# PowerReg.net
KiCad netlist of a schematic drawn in EAGLE
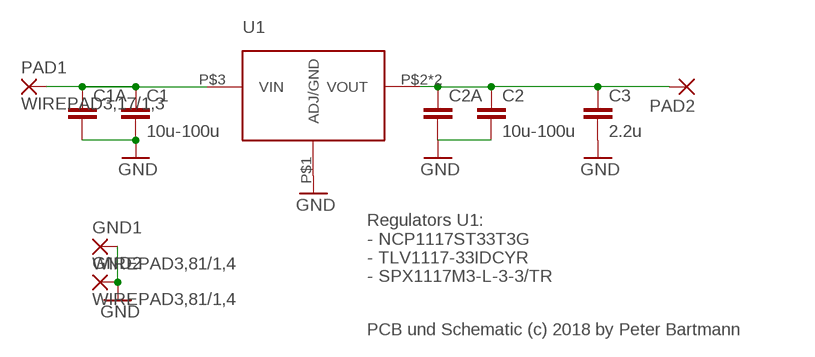
[diagram p0: schematic, sheet 1]

(export (version "E")
  (design (tool "Eeschema 10.0.6"))
  (components
    (comp (ref "C1")
      (value "10u-100u")
      (footprint "eagle-import:C0805")
      (libsource (lib "eagle-import") (part "rcl_334_C-EUC0805"))
    )
    (comp (ref "C1A")
      (value "C-EUC1210K")
      (footprint "eagle-import:C1210K")
      (libsource (lib "eagle-import") (part "C-EUC1210K"))
    )
    (comp (ref "C2")
      (value "10u-100u")
      (footprint "eagle-import:C0805")
      (libsource (lib "eagle-import") (part "rcl_334_C-EUC0805"))
    )
    (comp (ref "C2A")
      (value "C-EUC1210K")
      (footprint "eagle-import:C1210K")
      (libsource (lib "eagle-import") (part "C-EUC1210K"))
    )
    (comp (ref "C3")
      (value "2.2u")
      (footprint "eagle-import:C0603")
      (libsource (lib "eagle-import") (part "C-EUC0603"))
    )
    (comp (ref "GND1")
      (value "WIREPAD3,81/1,4")
      (footprint "eagle-import:3,81_1,4")
      (libsource (lib "eagle-import") (part "WIREPAD3,81/1,4"))
    )
    (comp (ref "GND2")
      (value "WIREPAD3,81/1,4")
      (footprint "eagle-import:3,81_1,4")
      (libsource (lib "eagle-import") (part "WIREPAD3,81/1,4"))
    )
    (comp (ref "PAD1")
      (value "WIREPAD3,17/1,3")
      (footprint "eagle-import:3,17_1,3")
      (libsource (lib "eagle-import") (part "WIREPAD3,17/1,3"))
    )
    (comp (ref "PAD2")
      (value "SMD5")
      (footprint "eagle-import:SMD2,54-5,08")
      (libsource (lib "eagle-import") (part "SMD5"))
    )
    (comp (ref "U1")
      (value "SPX1117")
      (footprint "eagle-import:SOT-223")
      (libsource (lib "eagle-import") (part "SPX1117"))
    )
  )
  (nets
    (net (code "1") (name "GND") (class "Default")
      (node (ref "C1") (pin "2") (pinfunction "2_2") (pintype "passive"))
      (node (ref "C1A") (pin "2") (pinfunction "2_2") (pintype "passive"))
      (node (ref "C2") (pin "2") (pinfunction "2_2") (pintype "passive"))
      (node (ref "C2A") (pin "2") (pinfunction "2_2") (pintype "passive"))
      (node (ref "C3") (pin "2") (pinfunction "2_2") (pintype "passive"))
      (node (ref "GND1") (pin "1") (pinfunction "P_1") (pintype "passive"))
      (node (ref "GND2") (pin "1") (pinfunction "P_1") (pintype "passive"))
      (node (ref "U1") (pin "P$1") (pinfunction "ADJ/GND_P$1") (pintype "bidirectional"))
    )
    (net (code "2") (name "Net-(PAD1-P)") (class "Default")
      (node (ref "C1") (pin "1") (pinfunction "1_1") (pintype "passive"))
      (node (ref "C1A") (pin "1") (pinfunction "1_1") (pintype "passive"))
      (node (ref "PAD1") (pin "1") (pinfunction "P_1") (pintype "passive"))
      (node (ref "U1") (pin "P$3") (pinfunction "VIN_P$3") (pintype "bidirectional"))
    )
    (net (code "3") (name "Net-(PAD2-P)") (class "Default")
      (node (ref "C2") (pin "1") (pinfunction "1_1") (pintype "passive"))
      (node (ref "C2A") (pin "1") (pinfunction "1_1") (pintype "passive"))
      (node (ref "C3") (pin "1") (pinfunction "1_1") (pintype "passive"))
      (node (ref "PAD2") (pin "1") (pinfunction "P_1") (pintype "passive"))
      (node (ref "U1") (pin "P$2") (pinfunction "VOUT_P$2") (pintype "bidirectional"))
      (node (ref "U1") (pin "P$4") (pinfunction "VOUT_P$4") (pintype "bidirectional"))
    )
  )
)
